# 74LS198.net
KiCad netlist of a schematic drawn in EAGLE
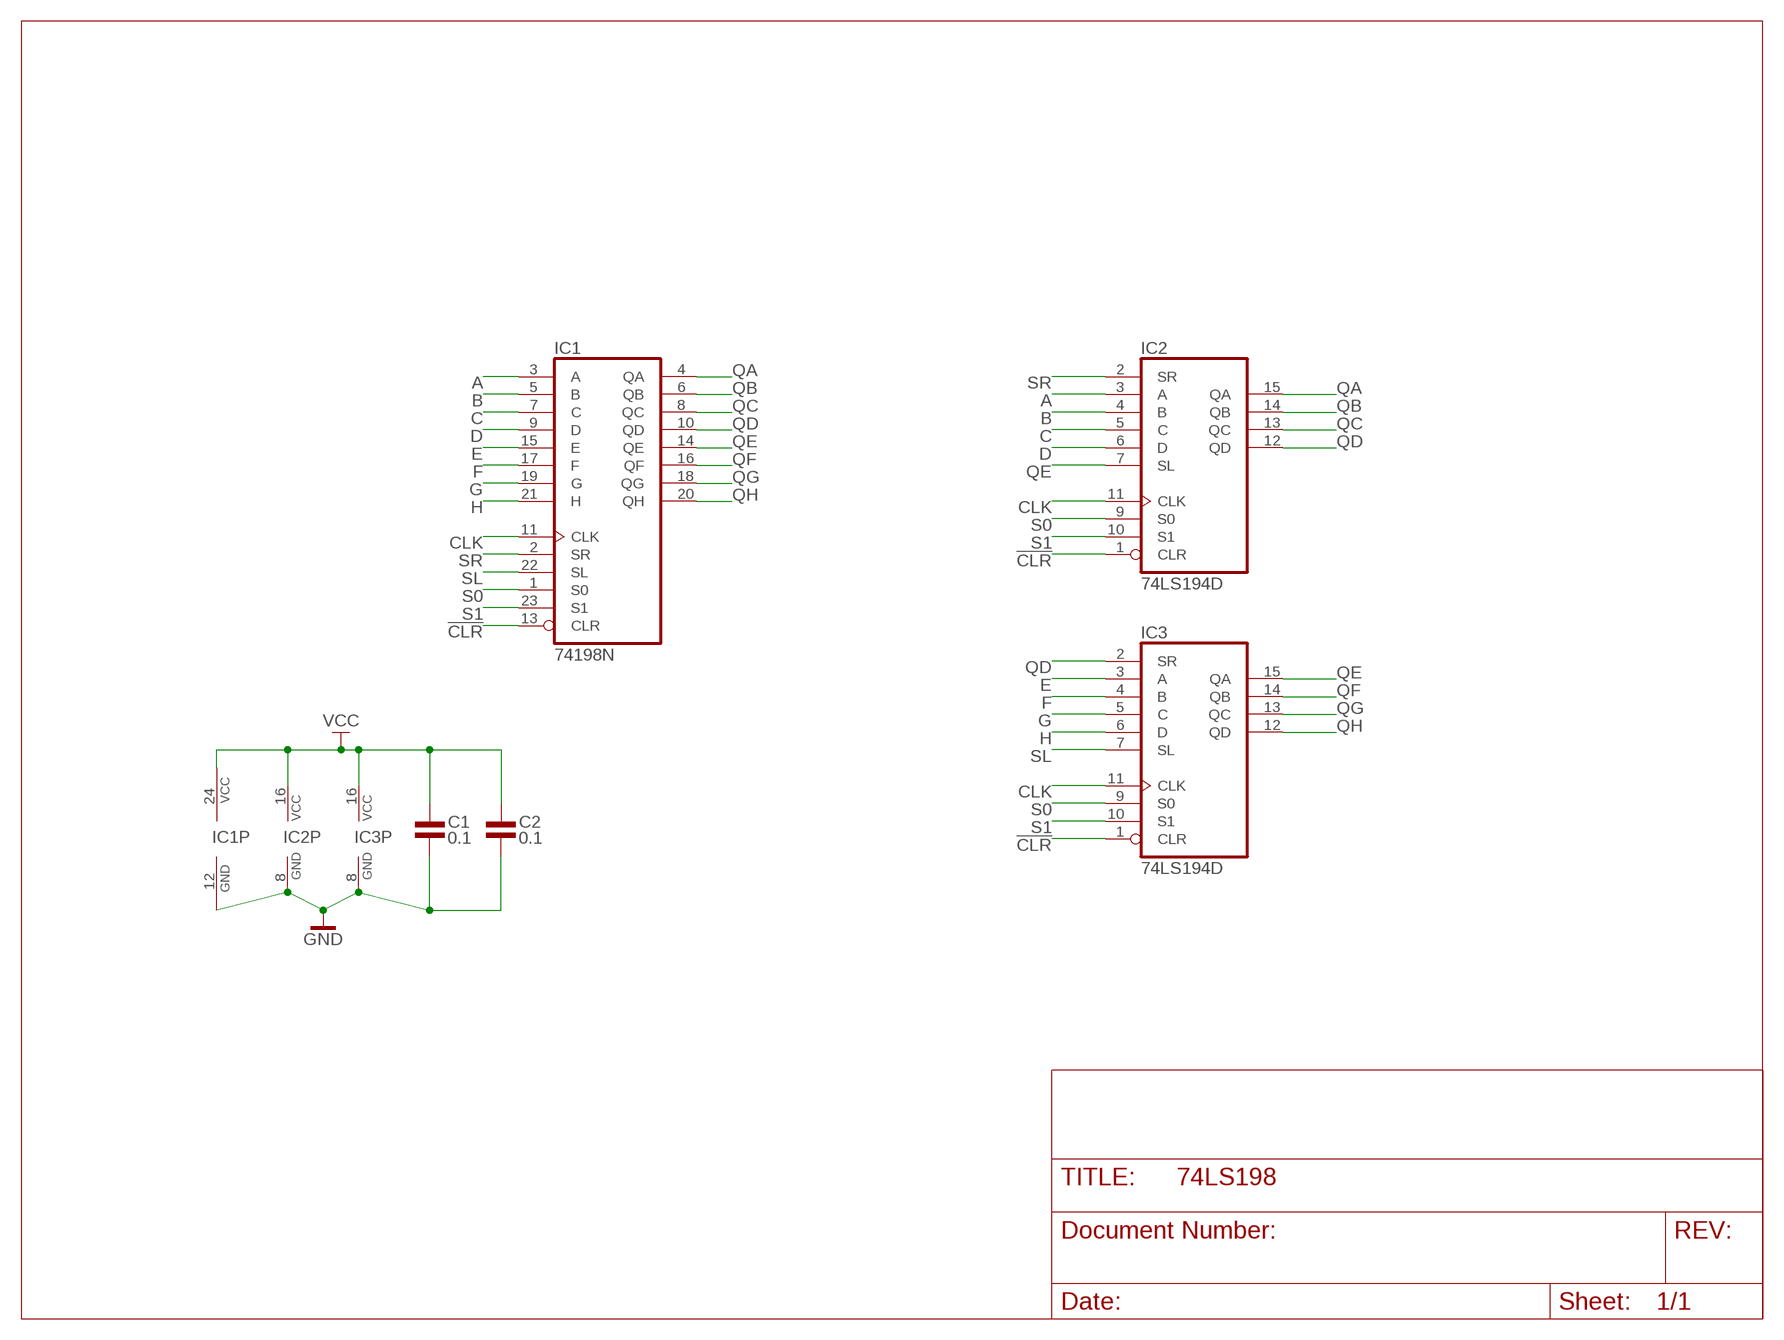
[diagram p0: schematic, sheet 1]

(export (version "E")
  (design (tool "Eeschema 10.0.6"))
  (components
    (comp (ref "C1")
      (value "0.1")
      (footprint "eagle-import:0805")
      (libsource (lib "eagle-import") (part "CAPACITOR_SMD0805"))
    )
    (comp (ref "C2")
      (value "0.1")
      (footprint "eagle-import:0805")
      (libsource (lib "eagle-import") (part "CAPACITOR_SMD0805"))
    )
    (comp (ref "IC1")
      (value "74198N")
      (footprint "eagle-import:DIP24W")
      (libsource (lib "eagle-import") (part "74198N"))
    )
    (comp (ref "IC2")
      (value "74LS194D")
      (footprint "eagle-import:SO16")
      (libsource (lib "eagle-import") (part "74194DLS"))
    )
    (comp (ref "IC3")
      (value "74LS194D")
      (footprint "eagle-import:SO16")
      (libsource (lib "eagle-import") (part "74194DLS"))
    )
  )
  (nets
    (net (code "1") (name "/A") (class "Default")
      (node (ref "IC1") (pin "3") (pinfunction "A_3") (pintype "input"))
      (node (ref "IC2") (pin "3") (pinfunction "A_3") (pintype "input"))
    )
    (net (code "2") (name "/B") (class "Default")
      (node (ref "IC1") (pin "5") (pinfunction "B_5") (pintype "input"))
      (node (ref "IC2") (pin "4") (pinfunction "B_4") (pintype "input"))
    )
    (net (code "3") (name "/C") (class "Default")
      (node (ref "IC1") (pin "7") (pinfunction "C_7") (pintype "input"))
      (node (ref "IC2") (pin "5") (pinfunction "C_5") (pintype "input"))
    )
    (net (code "4") (name "/CLK") (class "Default")
      (node (ref "IC1") (pin "11") (pinfunction "CLK_11") (pintype "input"))
      (node (ref "IC2") (pin "11") (pinfunction "CLK_11") (pintype "input"))
      (node (ref "IC3") (pin "11") (pinfunction "CLK_11") (pintype "input"))
    )
    (net (code "5") (name "/D") (class "Default")
      (node (ref "IC1") (pin "9") (pinfunction "D_9") (pintype "input"))
      (node (ref "IC2") (pin "6") (pinfunction "D_6") (pintype "input"))
    )
    (net (code "6") (name "/E") (class "Default")
      (node (ref "IC1") (pin "15") (pinfunction "E_15") (pintype "input"))
      (node (ref "IC3") (pin "3") (pinfunction "A_3") (pintype "input"))
    )
    (net (code "7") (name "/F") (class "Default")
      (node (ref "IC1") (pin "17") (pinfunction "F_17") (pintype "input"))
      (node (ref "IC3") (pin "4") (pinfunction "B_4") (pintype "input"))
    )
    (net (code "8") (name "/G") (class "Default")
      (node (ref "IC1") (pin "19") (pinfunction "G_19") (pintype "input"))
      (node (ref "IC3") (pin "5") (pinfunction "C_5") (pintype "input"))
    )
    (net (code "9") (name "/H") (class "Default")
      (node (ref "IC1") (pin "21") (pinfunction "H_21") (pintype "input"))
      (node (ref "IC3") (pin "6") (pinfunction "D_6") (pintype "input"))
    )
    (net (code "10") (name "/QA") (class "Default")
      (node (ref "IC1") (pin "4") (pinfunction "QA_4") (pintype "output"))
      (node (ref "IC2") (pin "15") (pinfunction "QA_15") (pintype "output"))
    )
    (net (code "11") (name "/QB") (class "Default")
      (node (ref "IC1") (pin "6") (pinfunction "QB_6") (pintype "output"))
      (node (ref "IC2") (pin "14") (pinfunction "QB_14") (pintype "output"))
    )
    (net (code "12") (name "/QC") (class "Default")
      (node (ref "IC1") (pin "8") (pinfunction "QC_8") (pintype "output"))
      (node (ref "IC2") (pin "13") (pinfunction "QC_13") (pintype "output"))
    )
    (net (code "13") (name "/QD") (class "Default")
      (node (ref "IC1") (pin "10") (pinfunction "QD_10") (pintype "output"))
      (node (ref "IC2") (pin "12") (pinfunction "QD_12") (pintype "output"))
      (node (ref "IC3") (pin "2") (pinfunction "SR_2") (pintype "input"))
    )
    (net (code "14") (name "/QE") (class "Default")
      (node (ref "IC1") (pin "14") (pinfunction "QE_14") (pintype "output"))
      (node (ref "IC2") (pin "7") (pinfunction "SL_7") (pintype "input"))
      (node (ref "IC3") (pin "15") (pinfunction "QA_15") (pintype "output"))
    )
    (net (code "15") (name "/QF") (class "Default")
      (node (ref "IC1") (pin "16") (pinfunction "QF_16") (pintype "output"))
      (node (ref "IC3") (pin "14") (pinfunction "QB_14") (pintype "output"))
    )
    (net (code "16") (name "/QG") (class "Default")
      (node (ref "IC1") (pin "18") (pinfunction "QG_18") (pintype "output"))
      (node (ref "IC3") (pin "13") (pinfunction "QC_13") (pintype "output"))
    )
    (net (code "17") (name "/QH") (class "Default")
      (node (ref "IC1") (pin "20") (pinfunction "QH_20") (pintype "output"))
      (node (ref "IC3") (pin "12") (pinfunction "QD_12") (pintype "output"))
    )
    (net (code "18") (name "/S0") (class "Default")
      (node (ref "IC1") (pin "1") (pinfunction "S0_1") (pintype "input"))
      (node (ref "IC2") (pin "9") (pinfunction "S0_9") (pintype "input"))
      (node (ref "IC3") (pin "9") (pinfunction "S0_9") (pintype "input"))
    )
    (net (code "19") (name "/S1") (class "Default")
      (node (ref "IC1") (pin "23") (pinfunction "S1_23") (pintype "input"))
      (node (ref "IC2") (pin "10") (pinfunction "S1_10") (pintype "input"))
      (node (ref "IC3") (pin "10") (pinfunction "S1_10") (pintype "input"))
    )
    (net (code "20") (name "/SL") (class "Default")
      (node (ref "IC1") (pin "22") (pinfunction "SL_22") (pintype "input"))
      (node (ref "IC3") (pin "7") (pinfunction "SL_7") (pintype "input"))
    )
    (net (code "21") (name "/SR") (class "Default")
      (node (ref "IC1") (pin "2") (pinfunction "SR_2") (pintype "input"))
      (node (ref "IC2") (pin "2") (pinfunction "SR_2") (pintype "input"))
    )
    (net (code "22") (name "/~{CLR}") (class "Default")
      (node (ref "IC1") (pin "13") (pinfunction "CLR_13") (pintype "input"))
      (node (ref "IC2") (pin "1") (pinfunction "CLR_1") (pintype "input"))
      (node (ref "IC3") (pin "1") (pinfunction "CLR_1") (pintype "input"))
    )
    (net (code "23") (name "GND") (class "Default")
      (node (ref "C1") (pin "1") (pinfunction "P$1_1") (pintype "passive"))
      (node (ref "C2") (pin "1") (pinfunction "P$1_1") (pintype "passive"))
      (node (ref "IC1") (pin "12") (pinfunction "GND_12") (pintype "power_in"))
      (node (ref "IC2") (pin "8") (pinfunction "GND_8") (pintype "power_in"))
      (node (ref "IC3") (pin "8") (pinfunction "GND_8") (pintype "power_in"))
    )
    (net (code "24") (name "VCC") (class "Default")
      (node (ref "C1") (pin "2") (pinfunction "P$2_2") (pintype "passive"))
      (node (ref "C2") (pin "2") (pinfunction "P$2_2") (pintype "passive"))
      (node (ref "IC1") (pin "24") (pinfunction "VCC_24") (pintype "power_in"))
      (node (ref "IC2") (pin "16") (pinfunction "VCC_16") (pintype "power_in"))
      (node (ref "IC3") (pin "16") (pinfunction "VCC_16") (pintype "power_in"))
    )
  )
)
